# Schematic.net
KiCad netlist of a schematic drawn in Altium Designer
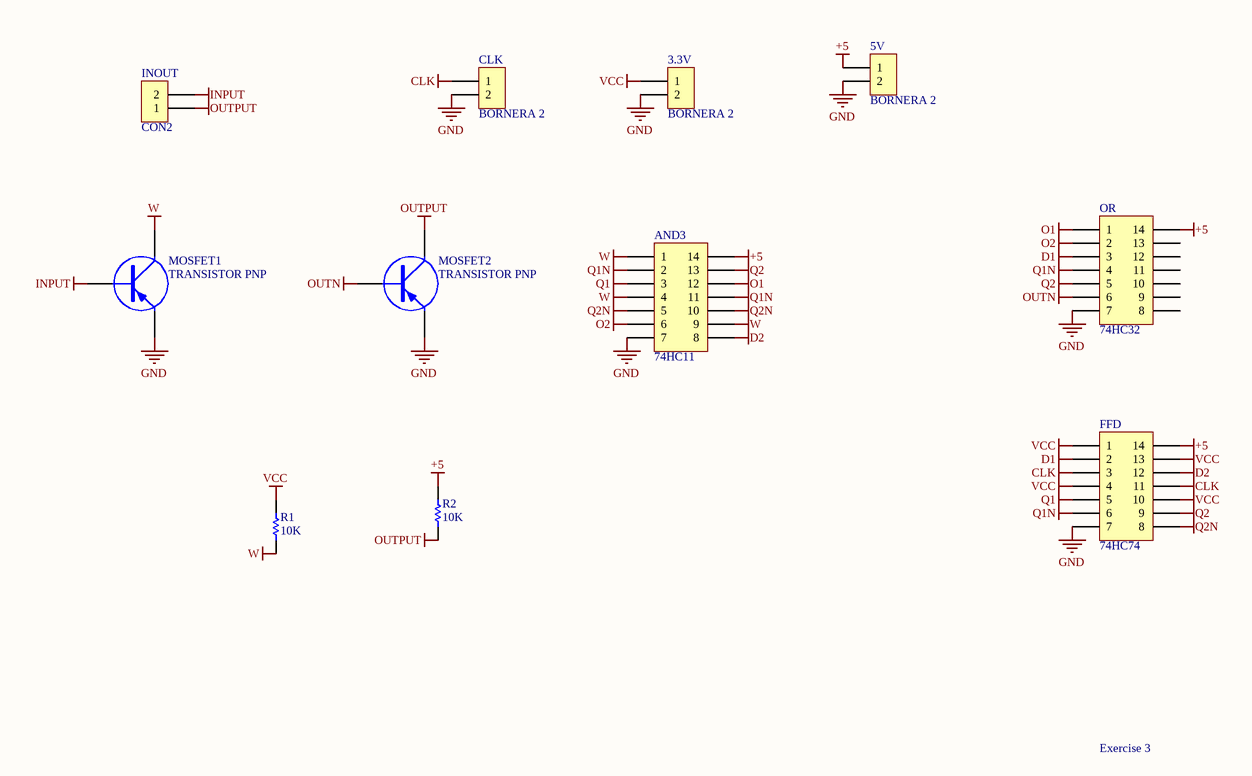
[diagram p0: Schematic.SchDoc]

(export (version "E")
  (design (tool "Eeschema 10.0.6"))
  (components
    (comp (ref "3.3V")
      (value "BORNERA 2")
      (footprint "BORNERA2")
      (libsource (lib "LIBEBAL") (part "BORNERA 2"))
    )
    (comp (ref "5V")
      (value "BORNERA 2")
      (footprint "BORNERA2")
      (libsource (lib "LIBEBAL") (part "BORNERA 2"))
    )
    (comp (ref "AND3") (value "74HC11") (footprint "DIP14") (libsource (lib "LIBEBAL") (part "IC_DIP14")))
    (comp (ref "CLK")
      (value "BORNERA 2")
      (footprint "BORNERA2")
      (libsource (lib "LIBEBAL") (part "BORNERA 2"))
    )
    (comp (ref "FFD") (value "74HC74") (footprint "DIP14") (libsource (lib "LIBEBAL") (part "IC_DIP14")))
    (comp (ref "INOUT") (value "CON2") (footprint "SIP2") (libsource (lib "LIBEBAL") (part "CON2")))
    (comp (ref "MOSFET1")
      (value "TRANSISTOR PNP")
      (footprint "TO92")
      (libsource (lib "LIBEBAL") (part "TRANSISTOR PNP"))
    )
    (comp (ref "MOSFET2")
      (value "TRANSISTOR PNP")
      (footprint "TO92")
      (libsource (lib "LIBEBAL") (part "TRANSISTOR PNP"))
    )
    (comp (ref "OR") (value "74HC32") (footprint "DIP14") (libsource (lib "LIBEBAL") (part "IC_DIP14")))
    (comp (ref "R1") (value "10K") (footprint "RES400") (libsource (lib "LIBEBAL") (part "RES")))
    (comp (ref "R2") (value "10K") (footprint "RES400") (libsource (lib "LIBEBAL") (part "RES")))
  )
  (nets
    (net (code "1") (name "+5") (class "Default")
      (node (ref "5V") (pin "1") (pinfunction "1_1") (pintype "passive"))
      (node (ref "AND3") (pin "14") (pinfunction "14_14") (pintype "passive"))
      (node (ref "FFD") (pin "14") (pinfunction "14_14") (pintype "passive"))
      (node (ref "OR") (pin "14") (pinfunction "14_14") (pintype "passive"))
      (node (ref "R2") (pin "2") (pinfunction "2_2") (pintype "passive"))
    )
    (net (code "2") (name "CLK") (class "Default")
      (node (ref "CLK") (pin "1") (pinfunction "1_1") (pintype "passive"))
      (node (ref "FFD") (pin "11") (pinfunction "11_11") (pintype "passive"))
      (node (ref "FFD") (pin "3") (pinfunction "3_3") (pintype "passive"))
    )
    (net (code "3") (name "D1") (class "Default")
      (node (ref "FFD") (pin "2") (pinfunction "2_2") (pintype "passive"))
      (node (ref "OR") (pin "3") (pinfunction "3_3") (pintype "passive"))
    )
    (net (code "4") (name "D2") (class "Default")
      (node (ref "AND3") (pin "8") (pinfunction "8_8") (pintype "passive"))
      (node (ref "FFD") (pin "12") (pinfunction "12_12") (pintype "passive"))
    )
    (net (code "5") (name "GND") (class "Default")
      (node (ref "3.3V") (pin "2") (pinfunction "2_2") (pintype "passive"))
      (node (ref "5V") (pin "2") (pinfunction "2_2") (pintype "passive"))
      (node (ref "AND3") (pin "7") (pinfunction "7_7") (pintype "passive"))
      (node (ref "CLK") (pin "2") (pinfunction "2_2") (pintype "passive"))
      (node (ref "FFD") (pin "7") (pinfunction "7_7") (pintype "passive"))
      (node (ref "MOSFET1") (pin "3") (pinfunction "E_3") (pintype "passive"))
      (node (ref "MOSFET2") (pin "3") (pinfunction "E_3") (pintype "passive"))
      (node (ref "OR") (pin "7") (pinfunction "7_7") (pintype "passive"))
    )
    (net (code "6") (name "INPUT") (class "Default")
      (node (ref "INOUT") (pin "2") (pinfunction "2_2") (pintype "passive"))
      (node (ref "MOSFET1") (pin "1") (pinfunction "B_1") (pintype "passive"))
    )
    (net (code "7") (name "O1") (class "Default")
      (node (ref "AND3") (pin "12") (pinfunction "12_12") (pintype "passive"))
      (node (ref "OR") (pin "1") (pinfunction "1_1") (pintype "passive"))
    )
    (net (code "8") (name "O2") (class "Default")
      (node (ref "AND3") (pin "6") (pinfunction "6_6") (pintype "passive"))
      (node (ref "OR") (pin "2") (pinfunction "2_2") (pintype "passive"))
    )
    (net (code "9") (name "OUTN") (class "Default")
      (node (ref "MOSFET2") (pin "1") (pinfunction "B_1") (pintype "passive"))
      (node (ref "OR") (pin "6") (pinfunction "6_6") (pintype "passive"))
    )
    (net (code "10") (name "OUTPUT") (class "Default")
      (node (ref "INOUT") (pin "1") (pinfunction "1_1") (pintype "passive"))
      (node (ref "MOSFET2") (pin "2") (pinfunction "C_2") (pintype "passive"))
      (node (ref "R2") (pin "1") (pinfunction "1_1") (pintype "passive"))
    )
    (net (code "11") (name "Q1") (class "Default")
      (node (ref "AND3") (pin "3") (pinfunction "3_3") (pintype "passive"))
      (node (ref "FFD") (pin "5") (pinfunction "5_5") (pintype "passive"))
    )
    (net (code "12") (name "Q1N") (class "Default")
      (node (ref "AND3") (pin "11") (pinfunction "11_11") (pintype "passive"))
      (node (ref "AND3") (pin "2") (pinfunction "2_2") (pintype "passive"))
      (node (ref "FFD") (pin "6") (pinfunction "6_6") (pintype "passive"))
      (node (ref "OR") (pin "4") (pinfunction "4_4") (pintype "passive"))
    )
    (net (code "13") (name "Q2") (class "Default")
      (node (ref "AND3") (pin "13") (pinfunction "13_13") (pintype "passive"))
      (node (ref "FFD") (pin "9") (pinfunction "9_9") (pintype "passive"))
      (node (ref "OR") (pin "5") (pinfunction "5_5") (pintype "passive"))
    )
    (net (code "14") (name "Q2N") (class "Default")
      (node (ref "AND3") (pin "10") (pinfunction "10_10") (pintype "passive"))
      (node (ref "AND3") (pin "5") (pinfunction "5_5") (pintype "passive"))
      (node (ref "FFD") (pin "8") (pinfunction "8_8") (pintype "passive"))
    )
    (net (code "15") (name "VCC") (class "Default")
      (node (ref "3.3V") (pin "1") (pinfunction "1_1") (pintype "passive"))
      (node (ref "FFD") (pin "1") (pinfunction "1_1") (pintype "passive"))
      (node (ref "FFD") (pin "10") (pinfunction "10_10") (pintype "passive"))
      (node (ref "FFD") (pin "13") (pinfunction "13_13") (pintype "passive"))
      (node (ref "FFD") (pin "4") (pinfunction "4_4") (pintype "passive"))
      (node (ref "R1") (pin "2") (pinfunction "2_2") (pintype "passive"))
    )
    (net (code "16") (name "W") (class "Default")
      (node (ref "AND3") (pin "1") (pinfunction "1_1") (pintype "passive"))
      (node (ref "AND3") (pin "4") (pinfunction "4_4") (pintype "passive"))
      (node (ref "AND3") (pin "9") (pinfunction "9_9") (pintype "passive"))
      (node (ref "MOSFET1") (pin "2") (pinfunction "C_2") (pintype "passive"))
      (node (ref "R1") (pin "1") (pinfunction "1_1") (pintype "passive"))
    )
    (net (code "17") (name "unconnected-(OR-Pad8)") (class "Default")
      (node (ref "OR") (pin "8") (pinfunction "8_8") (pintype "passive"))
    )
    (net (code "18") (name "unconnected-(OR-Pad9)") (class "Default")
      (node (ref "OR") (pin "9") (pinfunction "9_9") (pintype "passive"))
    )
    (net (code "19") (name "unconnected-(OR-Pad10)") (class "Default")
      (node (ref "OR") (pin "10") (pinfunction "10_10") (pintype "passive"))
    )
    (net (code "20") (name "unconnected-(OR-Pad11)") (class "Default")
      (node (ref "OR") (pin "11") (pinfunction "11_11") (pintype "passive"))
    )
    (net (code "21") (name "unconnected-(OR-Pad12)") (class "Default")
      (node (ref "OR") (pin "12") (pinfunction "12_12") (pintype "passive"))
    )
    (net (code "22") (name "unconnected-(OR-Pad13)") (class "Default")
      (node (ref "OR") (pin "13") (pinfunction "13_13") (pintype "passive"))
    )
  )
)
